# adalogger_shield_v1.net
KiCad netlist of a schematic drawn in EAGLE
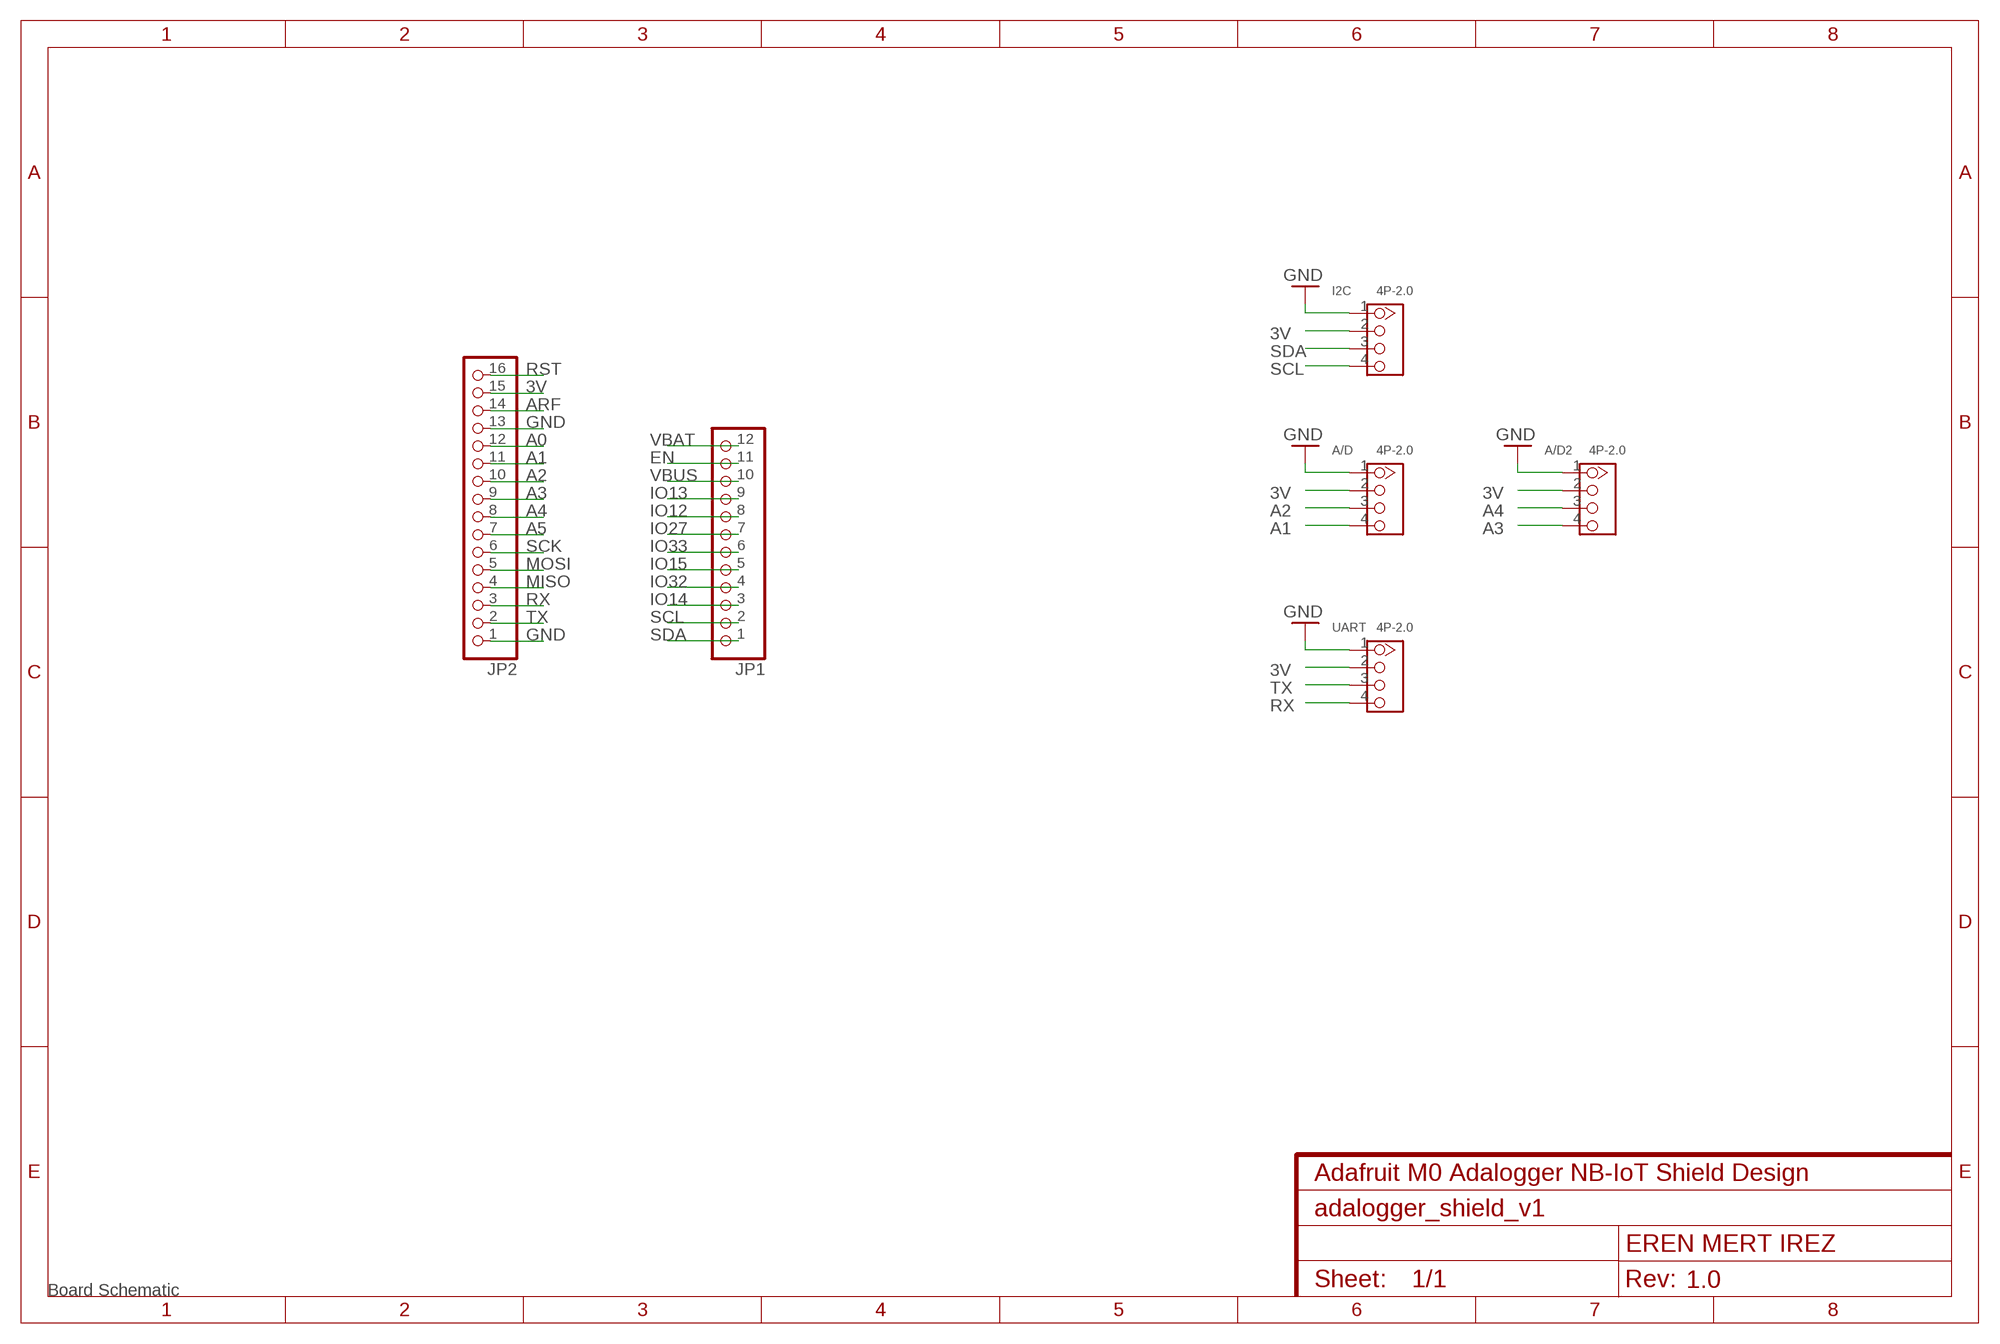
[diagram p0: schematic, sheet 1]

(export (version "E")
  (design (tool "Eeschema 10.0.6"))
  (components
    (comp (ref "A/D")
      (value "4P-2.0")
      (footprint "eagle-import:HW4-2.0")
      (libsource (lib "eagle-import") (part "GROVE-CONNECTOR-DIP(4P-2.0)"))
    )
    (comp (ref "A/D2")
      (value "4P-2.0")
      (footprint "eagle-import:HW4-2.0")
      (libsource (lib "eagle-import") (part "GROVE-CONNECTOR-DIP(4P-2.0)"))
    )
    (comp (ref "I2C")
      (value "4P-2.0")
      (footprint "eagle-import:HW4-2.0")
      (libsource (lib "eagle-import") (part "GROVE-CONNECTOR-DIP(4P-2.0)"))
    )
    (comp (ref "JP1")
      (value "HEADER-1X12")
      (footprint "eagle-import:1X12_ROUND")
      (libsource (lib "eagle-import") (part "HEADER-1X12"))
    )
    (comp (ref "JP2")
      (value "HEADER-1X16ROUND")
      (footprint "eagle-import:1X16_ROUND")
      (libsource (lib "eagle-import") (part "HEADER-1X16ROUND"))
    )
    (comp (ref "UART")
      (value "4P-2.0")
      (footprint "eagle-import:HW4-2.0")
      (libsource (lib "eagle-import") (part "GROVE-CONNECTOR-DIP(4P-2.0)"))
    )
  )
  (nets
    (net (code "1") (name "/3V") (class "Default")
      (node (ref "A/D") (pin "2") (pinfunction "2_2") (pintype "bidirectional"))
      (node (ref "A/D2") (pin "2") (pinfunction "2_2") (pintype "bidirectional"))
      (node (ref "I2C") (pin "2") (pinfunction "2_2") (pintype "bidirectional"))
      (node (ref "JP2") (pin "15") (pinfunction "15_15") (pintype "passive"))
      (node (ref "UART") (pin "2") (pinfunction "2_2") (pintype "bidirectional"))
    )
    (net (code "2") (name "/A0") (class "Default")
      (node (ref "JP2") (pin "12") (pinfunction "12_12") (pintype "passive"))
    )
    (net (code "3") (name "/A1") (class "Default")
      (node (ref "A/D") (pin "4") (pinfunction "4_4") (pintype "bidirectional"))
      (node (ref "JP2") (pin "11") (pinfunction "11_11") (pintype "passive"))
    )
    (net (code "4") (name "/A2") (class "Default")
      (node (ref "A/D") (pin "3") (pinfunction "3_3") (pintype "bidirectional"))
      (node (ref "JP2") (pin "10") (pinfunction "10_10") (pintype "passive"))
    )
    (net (code "5") (name "/A3") (class "Default")
      (node (ref "A/D2") (pin "4") (pinfunction "4_4") (pintype "bidirectional"))
      (node (ref "JP2") (pin "9") (pinfunction "9_9") (pintype "passive"))
    )
    (net (code "6") (name "/A4") (class "Default")
      (node (ref "A/D2") (pin "3") (pinfunction "3_3") (pintype "bidirectional"))
      (node (ref "JP2") (pin "8") (pinfunction "8_8") (pintype "passive"))
    )
    (net (code "7") (name "/A5") (class "Default")
      (node (ref "JP2") (pin "7") (pinfunction "7_7") (pintype "passive"))
    )
    (net (code "8") (name "/ARF") (class "Default")
      (node (ref "JP2") (pin "14") (pinfunction "14_14") (pintype "passive"))
    )
    (net (code "9") (name "/EN") (class "Default")
      (node (ref "JP1") (pin "11") (pinfunction "11_11") (pintype "passive"))
    )
    (net (code "10") (name "/IO12") (class "Default")
      (node (ref "JP1") (pin "8") (pinfunction "8_8") (pintype "passive"))
    )
    (net (code "11") (name "/IO13") (class "Default")
      (node (ref "JP1") (pin "9") (pinfunction "9_9") (pintype "passive"))
    )
    (net (code "12") (name "/IO14") (class "Default")
      (node (ref "JP1") (pin "3") (pinfunction "3_3") (pintype "passive"))
    )
    (net (code "13") (name "/IO15") (class "Default")
      (node (ref "JP1") (pin "5") (pinfunction "5_5") (pintype "passive"))
    )
    (net (code "14") (name "/IO27") (class "Default")
      (node (ref "JP1") (pin "7") (pinfunction "7_7") (pintype "passive"))
    )
    (net (code "15") (name "/IO32") (class "Default")
      (node (ref "JP1") (pin "4") (pinfunction "4_4") (pintype "passive"))
    )
    (net (code "16") (name "/IO33") (class "Default")
      (node (ref "JP1") (pin "6") (pinfunction "6_6") (pintype "passive"))
    )
    (net (code "17") (name "/MISO") (class "Default")
      (node (ref "JP2") (pin "4") (pinfunction "4_4") (pintype "passive"))
    )
    (net (code "18") (name "/MOSI") (class "Default")
      (node (ref "JP2") (pin "5") (pinfunction "5_5") (pintype "passive"))
    )
    (net (code "19") (name "/RST") (class "Default")
      (node (ref "JP2") (pin "16") (pinfunction "16_16") (pintype "passive"))
    )
    (net (code "20") (name "/RX") (class "Default")
      (node (ref "JP2") (pin "3") (pinfunction "3_3") (pintype "passive"))
      (node (ref "UART") (pin "4") (pinfunction "4_4") (pintype "bidirectional"))
    )
    (net (code "21") (name "/SCK") (class "Default")
      (node (ref "JP2") (pin "6") (pinfunction "6_6") (pintype "passive"))
    )
    (net (code "22") (name "/SCL") (class "Default")
      (node (ref "I2C") (pin "4") (pinfunction "4_4") (pintype "bidirectional"))
      (node (ref "JP1") (pin "2") (pinfunction "2_2") (pintype "passive"))
    )
    (net (code "23") (name "/SDA") (class "Default")
      (node (ref "I2C") (pin "3") (pinfunction "3_3") (pintype "bidirectional"))
      (node (ref "JP1") (pin "1") (pinfunction "1_1") (pintype "passive"))
    )
    (net (code "24") (name "/TX") (class "Default")
      (node (ref "JP2") (pin "2") (pinfunction "2_2") (pintype "passive"))
      (node (ref "UART") (pin "3") (pinfunction "3_3") (pintype "bidirectional"))
    )
    (net (code "25") (name "/VBAT") (class "Default")
      (node (ref "JP1") (pin "12") (pinfunction "12_12") (pintype "passive"))
    )
    (net (code "26") (name "/VBUS") (class "Default")
      (node (ref "JP1") (pin "10") (pinfunction "10_10") (pintype "passive"))
    )
    (net (code "27") (name "GND") (class "Default")
      (node (ref "A/D") (pin "1") (pinfunction "1_1") (pintype "bidirectional"))
      (node (ref "A/D2") (pin "1") (pinfunction "1_1") (pintype "bidirectional"))
      (node (ref "I2C") (pin "1") (pinfunction "1_1") (pintype "bidirectional"))
      (node (ref "JP2") (pin "1") (pinfunction "1_1") (pintype "passive"))
      (node (ref "JP2") (pin "13") (pinfunction "13_13") (pintype "passive"))
      (node (ref "UART") (pin "1") (pinfunction "1_1") (pintype "bidirectional"))
    )
  )
)
